# Standard_Bridge.net
KiCad netlist of a schematic drawn in Altium Designer
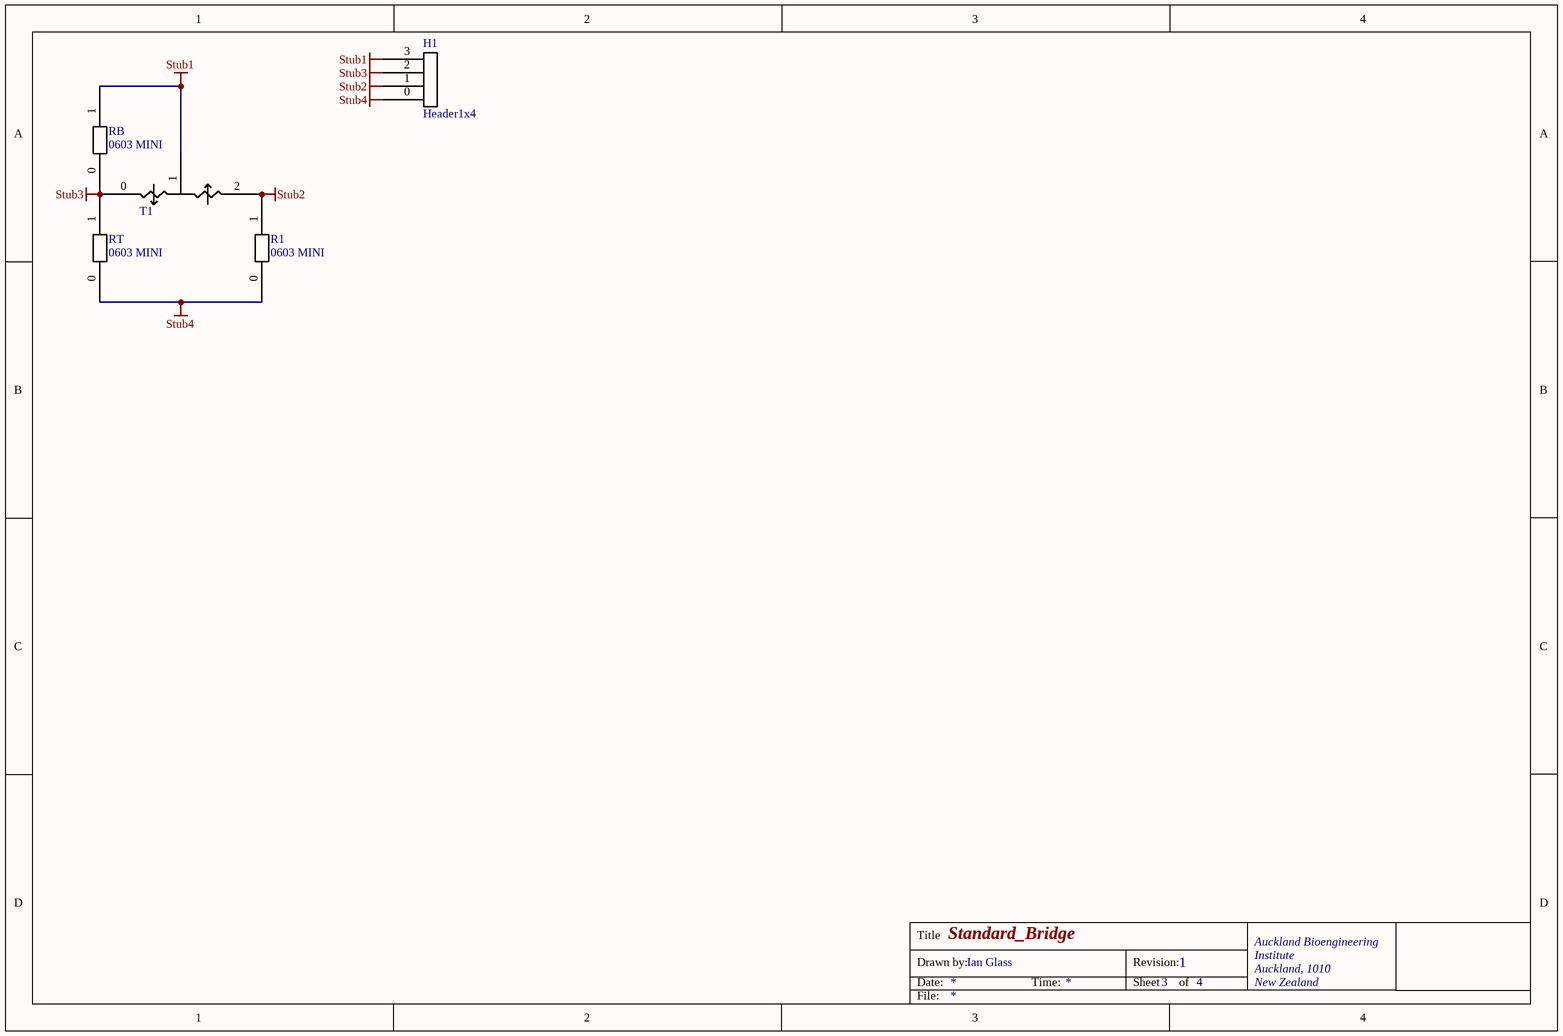
[diagram p0: Standard_Bridge.SchDoc]

(export (version "E")
  (design (tool "Eeschema 10.0.6"))
  (components
    (comp (ref "H1")
      (value "Header1x4")
      (footprint "PcbLib1:Header1x4")
      (libsource (lib "Schlib1") (part "Header1x4"))
    )
    (comp (ref "R1")
      (value "0603 MINI")
      (footprint "PcbLib1:0603 MINI")
      (libsource (lib "Schlib1") (part "0603 MINI"))
    )
    (comp (ref "RB")
      (value "0603 MINI")
      (footprint "PcbLib1:0603 MINI")
      (libsource (lib "Schlib1") (part "0603 MINI"))
    )
    (comp (ref "RT")
      (value "0603 MINI")
      (footprint "PcbLib1:0603 MINI")
      (libsource (lib "Schlib1") (part "0603 MINI"))
    )
    (comp (ref "T1")
      (value "Transducer")
      (footprint "PcbLib1:Transducer")
      (libsource (lib "Schlib1") (part "Transducer"))
    )
  )
  (nets
    (net (code "1") (name "Stub1") (class "Default")
      (node (ref "H1") (pin "3") (pinfunction "3_3") (pintype "passive"))
      (node (ref "RB") (pin "1") (pinfunction "1_1") (pintype "passive"))
      (node (ref "T1") (pin "1") (pinfunction "1_1") (pintype "passive"))
    )
    (net (code "2") (name "Stub2") (class "Default")
      (node (ref "H1") (pin "1") (pinfunction "1_1") (pintype "passive"))
      (node (ref "R1") (pin "1") (pinfunction "1_1") (pintype "passive"))
      (node (ref "T1") (pin "2") (pinfunction "2_2") (pintype "passive"))
    )
    (net (code "3") (name "Stub3") (class "Default")
      (node (ref "H1") (pin "2") (pinfunction "2_2") (pintype "passive"))
      (node (ref "RB") (pin "0") (pinfunction "0_0") (pintype "passive"))
      (node (ref "RT") (pin "1") (pinfunction "1_1") (pintype "passive"))
      (node (ref "T1") (pin "0") (pinfunction "0_0") (pintype "passive"))
    )
    (net (code "4") (name "Stub4") (class "Default")
      (node (ref "H1") (pin "0") (pinfunction "0_0") (pintype "passive"))
      (node (ref "R1") (pin "0") (pinfunction "0_0") (pintype "passive"))
      (node (ref "RT") (pin "0") (pinfunction "0_0") (pintype "passive"))
    )
  )
)
